# DS133-1_0-B.net
KiCad netlist of a schematic drawn in Altium Designer
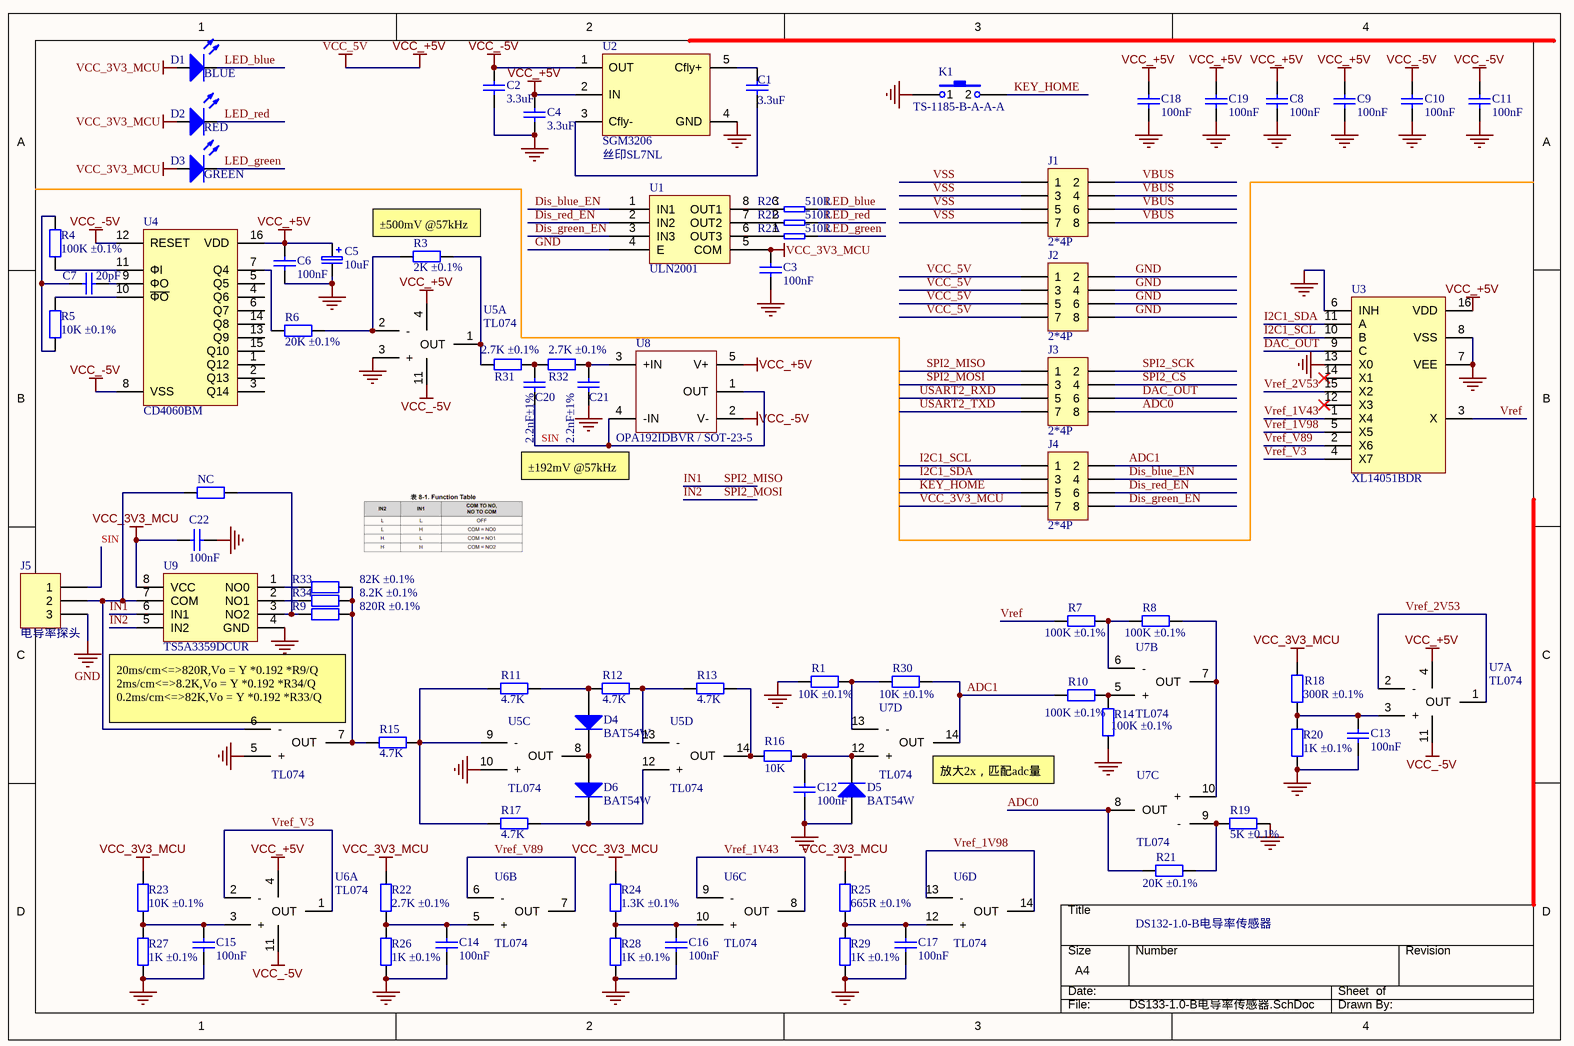
[diagram p0: DS133-1.0-B电导率传感器.SchDoc]

(export (version "E")
  (design (tool "Eeschema 10.0.6"))
  (components
    (comp (ref "C1")
      (value "3.3uF")
      (footprint "0603CAP")
      (description "贴片电容")
      (fields (field (name "Comment") "MLCC 3.3uF 50V ±10％ 0603"))
      (libsource (lib "AD_SCH") (part "MLCC 3.3uF 50V ±10％ 0603"))
    )
    (comp (ref "C2")
      (value "3.3uF")
      (footprint "0603CAP")
      (description "贴片电容")
      (libsource (lib "AD_SCH") (part "MLCC 3.3uF 50V ±10％ 0603"))
    )
    (comp (ref "C3")
      (value "100nF")
      (footprint "0603CAP")
      (description "贴片电容")
      (libsource (lib "AD_SCH") (part "MLCC 100nF 50V ±10％ 0603"))
    )
    (comp (ref "C4")
      (value "3.3uF")
      (footprint "0603CAP")
      (description "贴片电容")
      (fields (field (name "Comment") "MLCC 3.3uF 50V ±10％ 0603"))
      (libsource (lib "AD_SCH") (part "MLCC 3.3uF 50V ±10％ 0603"))
    )
    (comp (ref "C5")
      (value "10uF")
      (footprint "AVX_3216-18(1206)_SMD")
      (description "钽电容")
      (fields (field (name "Comment") "AVX_10uF/16V ±10％(C106)"))
      (libsource (lib "AD_SCH") (part "AVX_10uF/16V ±10％(C106)"))
    )
    (comp (ref "C6")
      (value "100nF")
      (footprint "0603CAP")
      (description "贴片电容")
      (fields (field (name "Comment") "SMDCAP00013"))
      (libsource (lib "AD_SCH") (part "MLCC 100nF 50V ±10％ 0603"))
    )
    (comp (ref "C7")
      (value "20pF")
      (footprint "0603CAP")
      (description "贴片电容")
      (fields (field (name "Comment") "SMDCAP00002"))
      (libsource (lib "AD_SCH") (part "MLCC 20pF 50V ±10％ 0603"))
    )
    (comp (ref "C8")
      (value "100nF")
      (footprint "0603CAP")
      (description "贴片电容")
      (libsource (lib "AD_SCH") (part "MLCC 100nF 50V ±10％ 0603"))
    )
    (comp (ref "C9")
      (value "100nF")
      (footprint "0603CAP")
      (description "贴片电容")
      (libsource (lib "AD_SCH") (part "MLCC 100nF 50V ±10％ 0603"))
    )
    (comp (ref "C10")
      (value "100nF")
      (footprint "0603CAP")
      (description "贴片电容")
      (libsource (lib "AD_SCH") (part "MLCC 100nF 50V ±10％ 0603"))
    )
    (comp (ref "C11")
      (value "100nF")
      (footprint "0603CAP")
      (description "贴片电容")
      (libsource (lib "AD_SCH") (part "MLCC 100nF 50V ±10％ 0603"))
    )
    (comp (ref "C12")
      (value "100nF")
      (footprint "0603CAP")
      (description "贴片电容")
      (libsource (lib "AD_SCH") (part "MLCC 100nF 50V ±10％ 0603"))
    )
    (comp (ref "C13")
      (value "100nF")
      (footprint "0603CAP")
      (description "贴片电容")
      (libsource (lib "AD_SCH") (part "MLCC 100nF 50V ±10％ 0603"))
    )
    (comp (ref "C14")
      (value "100nF")
      (footprint "0603CAP")
      (description "贴片电容")
      (libsource (lib "AD_SCH") (part "MLCC 100nF 50V ±10％ 0603"))
    )
    (comp (ref "C15")
      (value "100nF")
      (footprint "0603CAP")
      (description "贴片电容")
      (libsource (lib "AD_SCH") (part "MLCC 100nF 50V ±10％ 0603"))
    )
    (comp (ref "C16")
      (value "100nF")
      (footprint "0603CAP")
      (description "贴片电容")
      (libsource (lib "AD_SCH") (part "MLCC 100nF 50V ±10％ 0603"))
    )
    (comp (ref "C17")
      (value "100nF")
      (footprint "0603CAP")
      (description "贴片电容")
      (libsource (lib "AD_SCH") (part "MLCC 100nF 50V ±10％ 0603"))
    )
    (comp (ref "C18")
      (value "100nF")
      (footprint "0603CAP")
      (description "贴片电容")
      (libsource (lib "AD_SCH") (part "MLCC 100nF 50V ±10％ 0603"))
    )
    (comp (ref "C19")
      (value "100nF")
      (footprint "0603CAP")
      (description "贴片电容")
      (libsource (lib "AD_SCH") (part "MLCC 100nF 50V ±10％ 0603"))
    )
    (comp (ref "C20")
      (value "2.2nF±1%")
      (footprint "0603CAP")
      (description "贴片电容")
      (fields (field (name "Comment") "MLCC 2.2nF 50V ±1％ 0603"))
      (libsource (lib "AD_SCH") (part "MLCC 2.2nF 50V ±1％ 0603"))
    )
    (comp (ref "C21")
      (value "2.2nF±1%")
      (footprint "0603CAP")
      (description "贴片电容")
      (fields (field (name "Comment") "MLCC 2.2nF 50V ±1％ 0603"))
      (libsource (lib "AD_SCH") (part "MLCC 2.2nF 50V ±1％ 0603"))
    )
    (comp (ref "C22")
      (value "100nF")
      (footprint "0603CAP")
      (description "贴片电容")
      (libsource (lib "AD_SCH") (part "MLCC 100nF 50V ±10％ 0603"))
    )
    (comp (ref "D1")
      (value "BLUE")
      (footprint "LED_0805")
      (description "贴片LED")
      (fields (field (name "Comment") "SMDLED00010"))
      (libsource (lib "AD_SCH") (part "Chip 蓝色LED 0805"))
    )
    (comp (ref "D2")
      (value "RED")
      (footprint "LED_0805")
      (description "贴片LED")
      (fields (field (name "Comment") "SMDLED00003"))
      (libsource (lib "AD_SCH") (part "Chip 红色LED 0805"))
    )
    (comp (ref "D3")
      (value "GREEN")
      (footprint "LED_0805")
      (description "贴片LED")
      (fields (field (name "Comment") "Chip 翠绿LED 0805"))
      (libsource (lib "AD_SCH") (part "Chip 翠绿LED 0805"))
    )
    (comp (ref "D4") (value "BAT54W") (footprint "SOD-123") (libsource (lib "AD_SCH") (part "BAT54W")))
    (comp (ref "D5") (value "BAT54W") (footprint "SOD-123") (libsource (lib "AD_SCH") (part "BAT54W")))
    (comp (ref "D6") (value "BAT54W") (footprint "SOD-123") (libsource (lib "AD_SCH") (part "BAT54W")))
    (comp (ref "J1")
      (value "2*4P")
      (footprint "X1321WVS-2x04J-C40D53")
      (description "双排针2x4P 立贴 1.27mm")
      (fields (field (name "Comment") "X1321WVS-2x04J-C40D53"))
      (libsource (lib "AD_SCH") (part "X1321WVS-2x04J-C40D53"))
    )
    (comp (ref "J2")
      (value "2*4P")
      (footprint "X1321WVS-2x04J-C40D53")
      (description "双排针2x4P 立贴 1.27mm")
      (fields (field (name "Comment") "X1321WVS-2x04J-C40D53"))
      (libsource (lib "AD_SCH") (part "X1321WVS-2x04J-C40D53"))
    )
    (comp (ref "J3")
      (value "2*4P")
      (footprint "X1321WVS-2x04J-C40D53")
      (description "双排针2x4P 立贴 1.27mm")
      (fields (field (name "Comment") "X1321WVS-2x04J-C40D53"))
      (libsource (lib "AD_SCH") (part "X1321WVS-2x04J-C40D53"))
    )
    (comp (ref "J4")
      (value "2*4P")
      (footprint "X1321WVS-2x04J-C40D53")
      (description "双排针2x4P 立贴 1.27mm")
      (fields (field (name "Comment") "X1321WVS-2x04J-C40D53"))
      (libsource (lib "AD_SCH") (part "X1321WVS-2x04J-C40D53"))
    )
    (comp (ref "J5")
      (value "电导率探头")
      (footprint "SIP3")
      (description "单排直针")
      (fields (field (name "Comment") "SL000000042"))
      (libsource (lib "AD_SCH") (part "DIP3 单排直针 间距2.54mm 针长11mm 铜"))
    )
    (comp (ref "K1")
      (value "TS-1185-B-A-A-A")
      (footprint "KEY_TS-1185-x-A-A-A")
      (description "轻触开关")
      (libsource (lib "AD_SCH") (part "TS-1185-B-A-A-A"))
    )
    (comp (ref "NC")
      (value "Chip 0R 1/16W ±1％ 0603")
      (footprint "0603RES")
      (description "贴片电阻")
      (libsource (lib "AD_SCH") (part "Chip 0R 1/16W ±1％ 0603"))
    )
    (comp (ref "R1")
      (value "10K ±0.1%")
      (footprint "0603RES")
      (fields (field (name "Comment") "Chip 10K 1/10W ±0.1％ 0603"))
      (libsource (lib "") (part "Chip 10K 1/10W ±0.1％ 0603_1"))
    )
    (comp (ref "R2")
      (value "510R")
      (footprint "0603RES_Pack4")
      (description "贴片排阻")
      (fields (field (name "Comment") "SMDRES05003"))
      (libsource (lib "AD_SCH") (part "Chip R*4 510R 1/16W ±5％ 0603"))
    )
    (comp (ref "R3")
      (value "2K ±0.1%")
      (footprint "0603RES")
      (fields (field (name "Comment") "Chip 2K 1/10W ±0.1％ 0603"))
      (libsource (lib "AD_SCH") (part "Chip 2K 1/10W ±0.1％ 0603"))
    )
    (comp (ref "R4")
      (value "100K ±0.1%")
      (footprint "0603RES")
      (libsource (lib "") (part "Chip 100K 1/10W ±0.1％ 0603_1"))
    )
    (comp (ref "R5")
      (value "10K ±0.1%")
      (footprint "0603RES")
      (fields (field (name "Comment") "Chip 10K 1/10W ±0.1％ 0603"))
      (libsource (lib "AD_SCH") (part "Chip 10K 1/10W ±0.1％ 0603"))
    )
    (comp (ref "R6")
      (value "20K ±0.1%")
      (footprint "0603RES")
      (fields (field (name "Comment") "Chip 20K 1/10W ±0.1％ 0603"))
      (libsource (lib "AD_SCH") (part "Chip 20K 1/10W ±0.1％ 0603"))
    )
    (comp (ref "R7")
      (value "100K ±0.1%")
      (footprint "0603RES")
      (fields (field (name "Comment") "Chip 100K 1/10W ±0.1％ 0603"))
      (libsource (lib "AD_SCH") (part "Chip 100K 1/10W ±0.1％ 0603"))
    )
    (comp (ref "R8")
      (value "100K ±0.1%")
      (footprint "0603RES")
      (fields (field (name "Comment") "Chip 100K 1/10W ±0.1％ 0603"))
      (libsource (lib "") (part "Chip 100K 1/10W ±0.1％ 0603_2"))
    )
    (comp (ref "R9")
      (value "820R ±0.1%")
      (footprint "0603RES")
      (fields (field (name "Comment") "Chip 820R 1/10W ±0.1％ 0603"))
      (libsource (lib "AD_SCH") (part "Chip 820R 1/10W ±0.1％ 0603"))
    )
    (comp (ref "R10")
      (value "100K ±0.1%")
      (footprint "0603RES")
      (fields (field (name "Comment") "Chip 100K 1/10W ±0.1％ 0603"))
      (libsource (lib "AD_SCH") (part "Chip 100K 1/10W ±0.1％ 0603"))
    )
    (comp (ref "R11")
      (value "4.7K")
      (footprint "0603RES")
      (description "贴片电阻")
      (fields (field (name "Comment") "SMDRES00047"))
      (libsource (lib "AD_SCH") (part "Chip 4.7K 1/10W ±1％ 0603"))
    )
    (comp (ref "R12")
      (value "4.7K")
      (footprint "0603RES")
      (description "贴片电阻")
      (fields (field (name "Comment") "SMDRES00047"))
      (libsource (lib "AD_SCH") (part "Chip 4.7K 1/10W ±1％ 0603"))
    )
    (comp (ref "R13")
      (value "4.7K")
      (footprint "0603RES")
      (description "贴片电阻")
      (fields (field (name "Comment") "SMDRES00047"))
      (libsource (lib "AD_SCH") (part "Chip 4.7K 1/10W ±1％ 0603"))
    )
    (comp (ref "R14")
      (value "100K ±0.1%")
      (footprint "0603RES")
      (fields (field (name "Comment") "Chip 100K 1/10W ±0.1％ 0603"))
      (libsource (lib "") (part "Chip 100K 1/10W ±0.1％ 0603_1"))
    )
    (comp (ref "R15")
      (value "4.7K")
      (footprint "0603RES")
      (description "贴片电阻")
      (fields (field (name "Comment") "SMDRES00047"))
      (libsource (lib "AD_SCH") (part "Chip 4.7K 1/10W ±1％ 0603"))
    )
    (comp (ref "R16")
      (value "10K")
      (footprint "0603RES")
      (description "贴片电阻")
      (fields (field (name "Comment") "Chip 10K 1/16W ±1％ 0603"))
      (libsource (lib "AD_SCH") (part "Chip 10K 1/16W ±1％ 0603"))
    )
    (comp (ref "R17")
      (value "4.7K")
      (footprint "0603RES")
      (description "贴片电阻")
      (fields (field (name "Comment") "SMDRES00047"))
      (libsource (lib "AD_SCH") (part "Chip 4.7K 1/10W ±1％ 0603"))
    )
    (comp (ref "R18")
      (value "300R ±0.1%")
      (footprint "0603RES")
      (libsource (lib "AD_SCH") (part "Chip 300R 1/10W ±0.1％ 0603"))
    )
    (comp (ref "R19")
      (value "5K ±0.1%")
      (footprint "0603RES")
      (fields (field (name "Comment") "Chip 5K 1/10W ±0.1％ 0603"))
      (libsource (lib "AD_SCH") (part "Chip 5K 1/10W ±0.1％ 0603"))
    )
    (comp (ref "R20")
      (value "1K ±0.1%")
      (footprint "0603RES")
      (fields (field (name "Comment") "Chip 1K 1/10W ±0.1％ 0603"))
      (libsource (lib "AD_SCH") (part "Chip 1K 1/10W ±0.1％ 0603"))
    )
    (comp (ref "R21")
      (value "20K ±0.1%")
      (footprint "0603RES")
      (fields (field (name "Comment") "Chip 20K 1/10W ±0.1％ 0603"))
      (libsource (lib "AD_SCH") (part "Chip 20K 1/10W ±0.1％ 0603"))
    )
    (comp (ref "R22")
      (value "2.7K ±0.1%")
      (footprint "0603RES")
      (fields (field (name "Comment") "Chip 2.7K 1/10W ±0.1％ 0603"))
      (libsource (lib "") (part "Chip 2.7K 1/10W ±0.1％ 0603_1"))
    )
    (comp (ref "R23")
      (value "10K ±0.1%")
      (footprint "0603RES")
      (fields (field (name "Comment") "Chip 10K 1/10W ±0.1％ 0603"))
      (libsource (lib "AD_SCH") (part "Chip 10K 1/10W ±0.1％ 0603"))
    )
    (comp (ref "R24")
      (value "1.3K ±0.1%")
      (footprint "0603RES")
      (fields (field (name "Comment") "Chip 1.3K 1/10W ±0.1％ 0603"))
      (libsource (lib "AD_SCH") (part "Chip 1.3K 1/10W ±0.1％ 0603"))
    )
    (comp (ref "R25")
      (value "665R ±0.1%")
      (footprint "0603RES")
      (fields (field (name "Comment") "Chip 665R 1/10W ±0.1％ 0603"))
      (libsource (lib "AD_SCH") (part "Chip 665R 1/10W ±0.1％ 0603"))
    )
    (comp (ref "R26")
      (value "1K ±0.1%")
      (footprint "0603RES")
      (fields (field (name "Comment") "Chip 1K 1/10W ±0.1％ 0603"))
      (libsource (lib "AD_SCH") (part "Chip 1K 1/10W ±0.1％ 0603"))
    )
    (comp (ref "R27")
      (value "1K ±0.1%")
      (footprint "0603RES")
      (fields (field (name "Comment") "Chip 1K 1/10W ±0.1％ 0603"))
      (libsource (lib "AD_SCH") (part "Chip 1K 1/10W ±0.1％ 0603"))
    )
    (comp (ref "R28")
      (value "1K ±0.1%")
      (footprint "0603RES")
      (fields (field (name "Comment") "Chip 1K 1/10W ±0.1％ 0603"))
      (libsource (lib "AD_SCH") (part "Chip 1K 1/10W ±0.1％ 0603"))
    )
    (comp (ref "R29")
      (value "1K ±0.1%")
      (footprint "0603RES")
      (fields (field (name "Comment") "Chip 1K 1/10W ±0.1％ 0603"))
      (libsource (lib "AD_SCH") (part "Chip 1K 1/10W ±0.1％ 0603"))
    )
    (comp (ref "R30")
      (value "10K ±0.1%")
      (footprint "0603RES")
      (fields (field (name "Comment") "Chip 10K 1/10W ±0.1％ 0603"))
      (libsource (lib "") (part "Chip 10K 1/10W ±0.1％ 0603_1"))
    )
    (comp (ref "R31")
      (value "2.7K ±0.1%")
      (footprint "0603RES")
      (fields (field (name "Comment") "Chip 2.7K 1/10W ±0.1％ 0603"))
      (libsource (lib "AD_SCH") (part "Chip 2.7K 1/10W ±0.1％ 0603"))
    )
    (comp (ref "R32")
      (value "2.7K ±0.1%")
      (footprint "0603RES")
      (fields (field (name "Comment") "Chip 2.7K 1/10W ±0.1％ 0603"))
      (libsource (lib "AD_SCH") (part "Chip 2.7K 1/10W ±0.1％ 0603"))
    )
    (comp (ref "R33")
      (value "82K ±0.1%")
      (footprint "0603RES")
      (fields (field (name "Comment") "SMDRES00096"))
      (libsource (lib "AD_SCH") (part "Chip 82K 1/10W ±0.1％ 0603"))
    )
    (comp (ref "R34")
      (value "8.2K ±0.1%")
      (footprint "0603RES")
      (fields (field (name "Comment") "Chip 8.2k 1/10W ±0.1％ 0603"))
      (libsource (lib "AD_SCH") (part "Chip 8.2k 1/10W ±0.1％ 0603"))
    )
    (comp (ref "U1")
      (value "ULN2001")
      (footprint "SO-8")
      (description "电机驱动芯片")
      (fields (field (name "Comment") "SMDIC000018"))
      (libsource (lib "AD_SCH") (part "ULN2001 SOP-8"))
    )
    (comp (ref "U2")
      (value "SGM3206")
      (footprint "SOT23-5")
      (description "电荷泵芯片")
      (fields (field (name "ALTIUM_VALUE") "丝印SL7NL"))
      (libsource (lib "AD_SCH") (part "SGM3206"))
    )
    (comp (ref "U3")
      (value "XL14051BDR")
      (footprint "SO-16")
      (description "XINLUDA(信路达)\r\nXL14051BDR\r\nSOP-16​")
      (libsource (lib "AD_SCH") (part "XL14051BDR"))
    )
    (comp (ref "U4")
      (value "CD4060BM")
      (footprint "SO-16")
      (description "HGSEMI(华冠)\r\nCD4060BM/TR\r\nSOP-16")
      (libsource (lib "AD_SCH") (part "CD4060BM"))
    )
    (comp (ref "U5")
      (value "TL074")
      (footprint "SO-14")
      (description "TI\r\nTL074CDR\r\nSOIC-14")
      (libsource (lib "AD_SCH") (part "TL074"))
    )
    (comp (ref "U6")
      (value "TL074")
      (footprint "SO-14")
      (description "TI\r\nTL074CDR\r\nSOIC-14")
      (libsource (lib "AD_SCH") (part "TL074"))
    )
    (comp (ref "U7")
      (value "TL074")
      (footprint "SO-14")
      (description "TI\r\nTL074CDR\r\nSOIC-14")
      (libsource (lib "AD_SCH") (part "TL074"))
    )
    (comp (ref "U8")
      (value "OPA192IDBVR / SOT-23-5")
      (footprint "SOT23-5")
      (description "低失调电压: 65 µV（最大值）\r\n低输入偏置电流: 1 pA（最大值）\r\n单电源供电：2.7 V至5.5 V")
      (libsource (lib "AD_SCH") (part "AD8605"))
    )
    (comp (ref "U9")
      (value "TS5A3359DCUR")
      (footprint "VSSOP-8")
      (description "单刀三掷(SP3T)模拟开关")
      (libsource (lib "AD_SCH") (part "TS5A3359DCUR"))
    )
  )
  (nets
    (net (code "1") (name "/ADC0") (class "Default")
      (node (ref "J3") (pin "8") (pinfunction "8_8") (pintype "passive"))
      (node (ref "R21") (pin "1") (pinfunction "1_1") (pintype "passive"))
      (node (ref "U7") (pin "8") (pinfunction "OUT_8") (pintype "passive"))
    )
    (net (code "2") (name "/ADC1") (class "Default")
      (node (ref "J4") (pin "2") (pinfunction "2_2") (pintype "passive"))
      (node (ref "R10") (pin "1") (pinfunction "1_1") (pintype "passive"))
      (node (ref "R30") (pin "2") (pinfunction "2_2") (pintype "passive"))
      (node (ref "U7") (pin "14") (pinfunction "OUT_14") (pintype "passive"))
    )
    (net (code "3") (name "/DAC_OUT") (class "Default")
      (node (ref "J3") (pin "6") (pinfunction "6_6") (pintype "passive"))
      (node (ref "U3") (pin "9") (pinfunction "C_9") (pintype "passive"))
    )
    (net (code "4") (name "/Dis_blue_EN") (class "Default")
      (node (ref "J4") (pin "4") (pinfunction "4_4") (pintype "passive"))
      (node (ref "U1") (pin "1") (pinfunction "IN1_1") (pintype "passive"))
    )
    (net (code "5") (name "/Dis_green_EN") (class "Default")
      (node (ref "J4") (pin "8") (pinfunction "8_8") (pintype "passive"))
      (node (ref "U1") (pin "3") (pinfunction "IN3_3") (pintype "passive"))
    )
    (net (code "6") (name "/Dis_red_EN") (class "Default")
      (node (ref "J4") (pin "6") (pinfunction "6_6") (pintype "passive"))
      (node (ref "U1") (pin "2") (pinfunction "IN2_2") (pintype "passive"))
    )
    (net (code "7") (name "/I2C1_SCL") (class "Default")
      (node (ref "J4") (pin "1") (pinfunction "1_1") (pintype "passive"))
      (node (ref "U3") (pin "10") (pinfunction "B_10") (pintype "passive"))
    )
    (net (code "8") (name "/I2C1_SDA") (class "Default")
      (node (ref "J4") (pin "3") (pinfunction "3_3") (pintype "passive"))
      (node (ref "U3") (pin "11") (pinfunction "A_11") (pintype "passive"))
    )
    (net (code "9") (name "/IN1") (class "Default")
      (node (ref "J3") (pin "1") (pinfunction "1_1") (pintype "passive"))
      (node (ref "U9") (pin "6") (pinfunction "IN1_6") (pintype "passive"))
    )
    (net (code "10") (name "/IN2") (class "Default")
      (node (ref "J3") (pin "3") (pinfunction "3_3") (pintype "passive"))
      (node (ref "U9") (pin "5") (pinfunction "IN2_5") (pintype "passive"))
    )
    (net (code "11") (name "/KEY_HOME") (class "Default")
      (node (ref "J4") (pin "5") (pinfunction "5_5") (pintype "passive"))
      (node (ref "K1") (pin "2") (pinfunction "2_2") (pintype "passive"))
    )
    (net (code "12") (name "/LED_blue") (class "Default")
      (node (ref "D1") (pin "2") (pinfunction "K_2") (pintype "passive"))
      (node (ref "R2") (pin "6") (pinfunction "6_6") (pintype "passive"))
    )
    (net (code "13") (name "/LED_green") (class "Default")
      (node (ref "D3") (pin "2") (pinfunction "K_2") (pintype "passive"))
      (node (ref "R2") (pin "8") (pinfunction "8_8") (pintype "passive"))
    )
    (net (code "14") (name "/LED_red") (class "Default")
      (node (ref "D2") (pin "2") (pinfunction "K_2") (pintype "passive"))
      (node (ref "R2") (pin "7") (pinfunction "7_7") (pintype "passive"))
    )
    (net (code "15") (name "/SIN") (class "Default")
      (node (ref "C20") (pin "1") (pinfunction "1_1") (pintype "passive"))
      (node (ref "J5") (pin "1") (pinfunction "1_1") (pintype "passive"))
      (node (ref "U8") (pin "1") (pinfunction "OUT_1") (pintype "passive"))
      (node (ref "U8") (pin "4") (pinfunction "-IN_4") (pintype "passive"))
    )
    (net (code "16") (name "/SPI2_CS") (class "Default")
      (node (ref "J3") (pin "4") (pinfunction "4_4") (pintype "passive"))
    )
    (net (code "17") (name "/SPI2_SCK") (class "Default")
      (node (ref "J3") (pin "2") (pinfunction "2_2") (pintype "passive"))
    )
    (net (code "18") (name "/USART2_RXD") (class "Default")
      (node (ref "J3") (pin "5") (pinfunction "5_5") (pintype "passive"))
    )
    (net (code "19") (name "/USART2_TXD") (class "Default")
      (node (ref "J3") (pin "7") (pinfunction "7_7") (pintype "passive"))
    )
    (net (code "20") (name "/VBUS") (class "Default")
      (node (ref "J1") (pin "2") (pinfunction "2_2") (pintype "passive"))
      (node (ref "J1") (pin "4") (pinfunction "4_4") (pintype "passive"))
      (node (ref "J1") (pin "6") (pinfunction "6_6") (pintype "passive"))
      (node (ref "J1") (pin "8") (pinfunction "8_8") (pintype "passive"))
    )
    (net (code "21") (name "/VSS") (class "Default")
      (node (ref "J1") (pin "1") (pinfunction "1_1") (pintype "passive"))
      (node (ref "J1") (pin "3") (pinfunction "3_3") (pintype "passive"))
      (node (ref "J1") (pin "5") (pinfunction "5_5") (pintype "passive"))
      (node (ref "J1") (pin "7") (pinfunction "7_7") (pintype "passive"))
    )
    (net (code "22") (name "/Vref") (class "Default")
      (node (ref "R7") (pin "1") (pinfunction "1_1") (pintype "passive"))
      (node (ref "U3") (pin "3") (pinfunction "X_3") (pintype "passive"))
    )
    (net (code "23") (name "/Vref_1V43") (class "Default")
      (node (ref "U3") (pin "1") (pinfunction "X4_1") (pintype "passive"))
      (node (ref "U6") (pin "8") (pinfunction "OUT_8") (pintype "passive"))
      (node (ref "U6") (pin "9") (pinfunction "-_9") (pintype "passive"))
    )
    (net (code "24") (name "/Vref_1V98") (class "Default")
      (node (ref "U3") (pin "5") (pinfunction "X5_5") (pintype "passive"))
      (node (ref "U6") (pin "13") (pinfunction "-_13") (pintype "passive"))
      (node (ref "U6") (pin "14") (pinfunction "OUT_14") (pintype "passive"))
    )
    (net (code "25") (name "/Vref_2V53") (class "Default")
      (node (ref "U3") (pin "15") (pinfunction "X2_15") (pintype "passive"))
      (node (ref "U7") (pin "1") (pinfunction "OUT_1") (pintype "passive"))
      (node (ref "U7") (pin "2") (pinfunction "-_2") (pintype "passive"))
    )
    (net (code "26") (name "/Vref_V3") (class "Default")
      (node (ref "U3") (pin "4") (pinfunction "X7_4") (pintype "passive"))
      (node (ref "U6") (pin "1") (pinfunction "OUT_1") (pintype "passive"))
      (node (ref "U6") (pin "2") (pinfunction "-_2") (pintype "passive"))
    )
    (net (code "27") (name "/Vref_V89") (class "Default")
      (node (ref "U3") (pin "2") (pinfunction "X6_2") (pintype "passive"))
      (node (ref "U6") (pin "6") (pinfunction "-_6") (pintype "passive"))
      (node (ref "U6") (pin "7") (pinfunction "OUT_7") (pintype "passive"))
    )
    (net (code "28") (name "GND") (class "Default")
      (node (ref "C10") (pin "1") (pinfunction "1_1") (pintype "passive"))
      (node (ref "C11") (pin "1") (pinfunction "1_1") (pintype "passive"))
      (node (ref "C12") (pin "1") (pinfunction "1_1") (pintype "passive"))
      (node (ref "C13") (pin "2") (pinfunction "2_2") (pintype "passive"))
      (node (ref "C14") (pin "2") (pinfunction "2_2") (pintype "passive"))
      (node (ref "C15") (pin "2") (pinfunction "2_2") (pintype "passive"))
      (node (ref "C16") (pin "2") (pinfunction "2_2") (pintype "passive"))
      (node (ref "C17") (pin "2") (pinfunction "2_2") (pintype "passive"))
      (node (ref "C18") (pin "1") (pinfunction "1_1") (pintype "passive"))
      (node (ref "C19") (pin "1") (pinfunction "1_1") (pintype "passive"))
      (node (ref "C2") (pin "2") (pinfunction "2_2") (pintype "passive"))
      (node (ref "C21") (pin "1") (pinfunction "1_1") (pintype "passive"))
      (node (ref "C22") (pin "2") (pinfunction "2_2") (pintype "passive"))
      (node (ref "C3") (pin "1") (pinfunction "1_1") (pintype "passive"))
      (node (ref "C4") (pin "2") (pinfunction "2_2") (pintype "passive"))
      (node (ref "C5") (pin "2") (pinfunction "2_2") (pintype "passive"))
      (node (ref "C6") (pin "2") (pinfunction "2_2") (pintype "passive"))
      (node (ref "C8") (pin "1") (pinfunction "1_1") (pintype "passive"))
      (node (ref "C9") (pin "1") (pinfunction "1_1") (pintype "passive"))
      (node (ref "D5") (pin "1") (pinfunction "A_1") (pintype "passive"))
      (node (ref "J2") (pin "2") (pinfunction "2_2") (pintype "passive"))
      (node (ref "J2") (pin "4") (pinfunction "4_4") (pintype "passive"))
      (node (ref "J2") (pin "6") (pinfunction "6_6") (pintype "passive"))
      (node (ref "J2") (pin "8") (pinfunction "8_8") (pintype "passive"))
      (node (ref "J5") (pin "3") (pinfunction "3_3") (pintype "passive"))
      (node (ref "K1") (pin "1") (pinfunction "1_1") (pintype "passive"))
      (node (ref "R1") (pin "1") (pinfunction "1_1") (pintype "passive"))
      (node (ref "R14") (pin "1") (pinfunction "1_1") (pintype "passive"))
      (node (ref "R19") (pin "2") (pinfunction "2_2") (pintype "passive"))
      (node (ref "R20") (pin "1") (pinfunction "1_1") (pintype "passive"))
      (node (ref "R26") (pin "1") (pinfunction "1_1") (pintype "passive"))
      (node (ref "R27") (pin "1") (pinfunction "1_1") (pintype "passive"))
      (node (ref "R28") (pin "1") (pinfunction "1_1") (pintype "passive"))
      (node (ref "R29") (pin "1") (pinfunction "1_1") (pintype "passive"))
      (node (ref "U1") (pin "4") (pinfunction "E_4") (pintype "passive"))
      (node (ref "U2") (pin "4") (pinfunction "GND_4") (pintype "passive"))
      (node (ref "U3") (pin "13") (pinfunction "X0_13") (pintype "passive"))
      (node (ref "U3") (pin "6") (pinfunction "INH_6") (pintype "passive"))
      (node (ref "U3") (pin "7") (pinfunction "VEE_7") (pintype "passive"))
      (node (ref "U3") (pin "8") (pinfunction "VSS_8") (pintype "passive"))
      (node (ref "U5") (pin "10") (pinfunction "+_10") (pintype "passive"))
      (node (ref "U5") (pin "3") (pinfunction "+_3") (pintype "passive"))
      (node (ref "U5") (pin "5") (pinfunction "+_5") (pintype "passive"))
      (node (ref "U9") (pin "4") (pinfunction "GND_4") (pintype "passive"))
    )
    (net (code "29") (name "Net-(C7-Pad2)") (class "Default")
      (node (ref "C7") (pin "2") (pinfunction "2_2") (pintype "passive"))
      (node (ref "R4") (pin "2") (pinfunction "2_2") (pintype "passive"))
      (node (ref "R5") (pin "1") (pinfunction "1_1") (pintype "passive"))
    )
    (net (code "30") (name "Net-(C20-Pad2)") (class "Default")
      (node (ref "C20") (pin "2") (pinfunction "2_2") (pintype "passive"))
      (node (ref "R31") (pin "2") (pinfunction "2_2") (pintype "passive"))
      (node (ref "R32") (pin "1") (pinfunction "1_1") (pintype "passive"))
    )
    (net (code "31") (name "Net-(D4-A)") (class "Default")
      (node (ref "D4") (pin "1") (pinfunction "A_1") (pintype "passive"))
      (node (ref "R11") (pin "2") (pinfunction "2_2") (pintype "passive"))
      (node (ref "R12") (pin "1") (pinfunction "1_1") (pintype "passive"))
    )
    (net (code "32") (name "Net-(D4-K)") (class "Default")
      (node (ref "D4") (pin "2") (pinfunction "K_2") (pintype "passive"))
      (node (ref "D6") (pin "1") (pinfunction "A_1") (pintype "passive"))
      (node (ref "U5") (pin "8") (pinfunction "OUT_8") (pintype "passive"))
    )
    (net (code "33") (name "Net-(D5-K)") (class "Default")
      (node (ref "C12") (pin "2") (pinfunction "2_2") (pintype "passive"))
      (node (ref "D5") (pin "2") (pinfunction "K_2") (pintype "passive"))
      (node (ref "R16") (pin "2") (pinfunction "2_2") (pintype "passive"))
      (node (ref "U7") (pin "12") (pinfunction "+_12") (pintype "passive"))
    )
    (net (code "34") (name "Net-(D6-K)") (class "Default")
      (node (ref "D6") (pin "2") (pinfunction "K_2") (pintype "passive"))
      (node (ref "R17") (pin "2") (pinfunction "2_2") (pintype "passive"))
      (node (ref "U5") (pin "12") (pinfunction "+_12") (pintype "passive"))
    )
    (net (code "35") (name "Net-(U1-OUT1)") (class "Default")
      (node (ref "R2") (pin "3") (pinfunction "3_3") (pintype "passive"))
      (node (ref "U1") (pin "8") (pinfunction "OUT1_8") (pintype "passive"))
    )
    (net (code "36") (name "Net-(U1-OUT2)") (class "Default")
      (node (ref "R2") (pin "2") (pinfunction "2_2") (pintype "passive"))
      (node (ref "U1") (pin "7") (pinfunction "OUT2_7") (pintype "passive"))
    )
    (net (code "37") (name "Net-(U1-OUT3)") (class "Default")
      (node (ref "R2") (pin "1") (pinfunction "1_1") (pintype "passive"))
      (node (ref "U1") (pin "6") (pinfunction "OUT3_6") (pintype "passive"))
    )
    (net (code "38") (name "Net-(U2-Cfly+)") (class "Default")
      (node (ref "C1") (pin "2") (pinfunction "2_2") (pintype "passive"))
      (node (ref "U2") (pin "5") (pinfunction "Cfly+_5") (pintype "passive"))
    )
    (net (code "39") (name "Net-(U2-Cfly-)") (class "Default")
      (node (ref "C1") (pin "1") (pinfunction "1_1") (pintype "passive"))
      (node (ref "U2") (pin "3") (pinfunction "Cfly-_3") (pintype "passive"))
    )
    (net (code "40") (name "Net-(U4-Q4)") (class "Default")
      (node (ref "R6") (pin "1") (pinfunction "1_1") (pintype "passive"))
      (node (ref "U4") (pin "7") (pinfunction "Q4_7") (pintype "passive"))
    )
    (net (code "41") (name "Net-(U4-~{ΦO})") (class "Default")
      (node (ref "R5") (pin "2") (pinfunction "2_2") (pintype "passive"))
      (node (ref "U4") (pin "10") (pinfunction "~{ΦO}_10") (pintype "passive"))
    )
    (net (code "42") (name "Net-(U4-ΦI)") (class "Default")
      (node (ref "R4") (pin "1") (pinfunction "1_1") (pintype "passive"))
      (node (ref "U4") (pin "11") (pinfunction "ΦI_11") (pintype "passive"))
    )
    (net (code "43") (name "Net-(U4-ΦO)") (class "Default")
      (node (ref "C7") (pin "1") (pinfunction "1_1") (pintype "passive"))
      (node (ref "U4") (pin "9") (pinfunction "ΦO_9") (pintype "passive"))
    )
    (net (code "44") (name "Net-(U5A--)") (class "Default")
      (node (ref "R3") (pin "1") (pinfunction "1_1") (pintype "passive"))
      (node (ref "R6") (pin "2") (pinfunction "2_2") (pintype "passive"))
      (node (ref "U5") (pin "2") (pinfunction "-_2") (pintype "passive"))
    )
    (net (code "45") (name "Net-(U5A-OUT)") (class "Default")
      (node (ref "R3") (pin "2") (pinfunction "2_2") (pintype "passive"))
      (node (ref "R31") (pin "1") (pinfunction "1_1") (pintype "passive"))
      (node (ref "U5") (pin "1") (pinfunction "OUT_1") (pintype "passive"))
    )
    (net (code "46") (name "Net-(U5B--)") (class "Default")
      (node (ref "J5") (pin "2") (pinfunction "2_2") (pintype "passive"))
      (node (ref "NC") (pin "1") (pinfunction "1_1") (pintype "passive"))
      (node (ref "U5") (pin "6") (pinfunction "-_6") (pintype "passive"))
      (node (ref "U9") (pin "7") (pinfunction "COM_7") (pintype "passive"))
    )
    (net (code "47") (name "Net-(U5B-OUT)") (class "Default")
      (node (ref "R15") (pin "1") (pinfunction "1_1") (pintype "passive"))
      (node (ref "R33") (pin "2") (pinfunction "2_2") (pintype "passive"))
      (node (ref "R34") (pin "2") (pinfunction "2_2") (pintype "passive"))
      (node (ref "R9") (pin "2") (pinfunction "2_2") (pintype "passive"))
      (node (ref "U5") (pin "7") (pinfunction "OUT_7") (pintype "passive"))
    )
    (net (code "48") (name "Net-(U5C--)") (class "Default")
      (node (ref "R11") (pin "1") (pinfunction "1_1") (pintype "passive"))
      (node (ref "R15") (pin "2") (pinfunction "2_2") (pintype "passive"))
      (node (ref "R17") (pin "1") (pinfunction "1_1") (pintype "passive"))
      (node (ref "U5") (pin "9") (pinfunction "-_9") (pintype "passive"))
    )
    (net (code "49") (name "Net-(U5D--)") (class "Default")
      (node (ref "R12") (pin "2") (pinfunction "2_2") (pintype "passive"))
      (node (ref "R13") (pin "1") (pinfunction "1_1") (pintype "passive"))
      (node (ref "U5") (pin "13") (pinfunction "-_13") (pintype "passive"))
    )
    (net (code "50") (name "Net-(U5D-OUT)") (class "Default")
      (node (ref "R13") (pin "2") (pinfunction "2_2") (pintype "passive"))
      (node (ref "R16") (pin "1") (pinfunction "1_1") (pintype "passive"))
      (node (ref "U5") (pin "14") (pinfunction "OUT_14") (pintype "passive"))
    )
    (net (code "51") (name "Net-(U6A-+)") (class "Default")
      (node (ref "C15") (pin "1") (pinfunction "1_1") (pintype "passive"))
      (node (ref "R23") (pin "1") (pinfunction "1_1") (pintype "passive"))
      (node (ref "R27") (pin "2") (pinfunction "2_2") (pintype "passive"))
      (node (ref "U6") (pin "3") (pinfunction "+_3") (pintype "passive"))
    )
    (net (code "52") (name "Net-(U6B-+)") (class "Default")
      (node (ref "C14") (pin "1") (pinfunction "1_1") (pintype "passive"))
      (node (ref "R22") (pin "1") (pinfunction "1_1") (pintype "passive"))
      (node (ref "R26") (pin "2") (pinfunction "2_2") (pintype "passive"))
      (node (ref "U6") (pin "5") (pinfunction "+_5") (pintype "passive"))
    )
    (net (code "53") (name "Net-(U6C-+)") (class "Default")
      (node (ref "C16") (pin "1") (pinfunction "1_1") (pintype "passive"))
      (node (ref "R24") (pin "1") (pinfunction "1_1") (pintype "passive"))
      (node (ref "R28") (pin "2") (pinfunction "2_2") (pintype "passive"))
      (node (ref "U6") (pin "10") (pinfunction "+_10") (pintype "passive"))
    )
    (net (code "54") (name "Net-(U6D-+)") (class "Default")
      (node (ref "C17") (pin "1") (pinfunction "1_1") (pintype "passive"))
      (node (ref "R25") (pin "1") (pinfunction "1_1") (pintype "passive"))
      (node (ref "R29") (pin "2") (pinfunction "2_2") (pintype "passive"))
      (node (ref "U6") (pin "12") (pinfunction "+_12") (pintype "passive"))
    )
    (net (code "55") (name "Net-(U7A-+)") (class "Default")
      (node (ref "C13") (pin "1") (pinfunction "1_1") (pintype "passive"))
      (node (ref "R18") (pin "1") (pinfunction "1_1") (pintype "passive"))
      (node (ref "R20") (pin "2") (pinfunction "2_2") (pintype "passive"))
      (node (ref "U7") (pin "3") (pinfunction "+_3") (pintype "passive"))
    )
    (net (code "56") (name "Net-(U7B-+)") (class "Default")
      (node (ref "R10") (pin "2") (pinfunction "2_2") (pintype "passive"))
      (node (ref "R14") (pin "2") (pinfunction "2_2") (pintype "passive"))
      (node (ref "U7") (pin "5") (pinfunction "+_5") (pintype "passive"))
    )
    (net (code "57") (name "Net-(U7B--)") (class "Default")
      (node (ref "R7") (pin "2") (pinfunction "2_2") (pintype "passive"))
      (node (ref "R8") (pin "2") (pinfunction "2_2") (pintype "passive"))
      (node (ref "U7") (pin "6") (pinfunction "-_6") (pintype "passive"))
    )
    (net (code "58") (name "Net-(U7B-OUT)") (class "Default")
      (node (ref "R8") (pin "1") (pinfunction "1_1") (pintype "passive"))
      (node (ref "U7") (pin "10") (pinfunction "+_10") (pintype "passive"))
      (node (ref "U7") (pin "7") (pinfunction "OUT_7") (pintype "passive"))
    )
    (net (code "59") (name "Net-(U7C--)") (class "Default")
      (node (ref "R19") (pin "1") (pinfunction "1_1") (pintype "passive"))
      (node (ref "R21") (pin "2") (pinfunction "2_2") (pintype "passive"))
      (node (ref "U7") (pin "9") (pinfunction "-_9") (pintype "passive"))
    )
    (net (code "60") (name "Net-(U7D--)") (class "Default")
      (node (ref "R1") (pin "2") (pinfunction "2_2") (pintype "passive"))
      (node (ref "R30") (pin "1") (pinfunction "1_1") (pintype "passive"))
      (node (ref "U7") (pin "13") (pinfunction "-_13") (pintype "passive"))
    )
    (net (code "61") (name "Net-(U8-+IN)") (class "Default")
      (node (ref "C21") (pin "2") (pinfunction "2_2") (pintype "passive"))
      (node (ref "R32") (pin "2") (pinfunction "2_2") (pintype "passive"))
      (node (ref "U8") (pin "3") (pinfunction "+IN_3") (pintype "passive"))
    )
    (net (code "62") (name "Net-(U9-NO0)") (class "Default")
      (node (ref "R33") (pin "1") (pinfunction "1_1") (pintype "passive"))
      (node (ref "U9") (pin "1") (pinfunction "NO0_1") (pintype "passive"))
    )
    (net (code "63") (name "Net-(U9-NO1)") (class "Default")
      (node (ref "R34") (pin "1") (pinfunction "1_1") (pintype "passive"))
      (node (ref "U9") (pin "2") (pinfunction "NO1_2") (pintype "passive"))
    )
    (net (code "64") (name "Net-(U9-NO2)") (class "Default")
      (node (ref "NC") (pin "2") (pinfunction "2_2") (pintype "passive"))
      (node (ref "R9") (pin "1") (pinfunction "1_1") (pintype "passive"))
      (node (ref "U9") (pin "3") (pinfunction "NO2_3") (pintype "passive"))
    )
    (net (code "65") (name "VCC_+5V") (class "Default")
      (node (ref "C18") (pin "2") (pinfunction "2_2") (pintype "passive"))
      (node (ref "C19") (pin "2") (pinfunction "2_2") (pintype "passive"))
      (node (ref "C4") (pin "1") (pinfunction "1_1") (pintype "passive"))
      (node (ref "C5") (pin "1") (pinfunction "1_1") (pintype "passive"))
      (node (ref "C6") (pin "1") (pinfunction "1_1") (pintype "passive"))
      (node (ref "C8") (pin "2") (pinfunction "2_2") (pintype "passive"))
      (node (ref "C9") (pin "2") (pinfunction "2_2") (pintype "passive"))
      (node (ref "J2") (pin "1") (pinfunction "1_1") (pintype "passive"))
      (node (ref "J2") (pin "3") (pinfunction "3_3") (pintype "passive"))
      (node (ref "J2") (pin "5") (pinfunction "5_5") (pintype "passive"))
      (node (ref "J2") (pin "7") (pinfunction "7_7") (pintype "passive"))
      (node (ref "U2") (pin "2") (pinfunction "IN_2") (pintype "passive"))
      (node (ref "U3") (pin "16") (pinfunction "VDD_16") (pintype "passive"))
      (node (ref "U4") (pin "16") (pinfunction "VDD_16") (pintype "passive"))
      (node (ref "U5") (pin "4") (pinfunction "VCC_4") (pintype "passive"))
      (node (ref "U6") (pin "4") (pinfunction "VCC_4") (pintype "passive"))
      (node (ref "U7") (pin "4") (pinfunction "VCC_4") (pintype "passive"))
      (node (ref "U8") (pin "5") (pinfunction "V+_5") (pintype "passive"))
    )
    (net (code "66") (name "VCC_-5V") (class "Default")
      (node (ref "C10") (pin "2") (pinfunction "2_2") (pintype "passive"))
      (node (ref "C11") (pin "2") (pinfunction "2_2") (pintype "passive"))
      (node (ref "C2") (pin "1") (pinfunction "1_1") (pintype "passive"))
      (node (ref "U2") (pin "1") (pinfunction "OUT_1") (pintype "passive"))
      (node (ref "U4") (pin "12") (pinfunction "RESET_12") (pintype "passive"))
      (node (ref "U4") (pin "8") (pinfunction "VSS_8") (pintype "passive"))
      (node (ref "U5") (pin "11") (pinfunction "GND_11") (pintype "passive"))
      (node (ref "U6") (pin "11") (pinfunction "GND_11") (pintype "passive"))
      (node (ref "U7") (pin "11") (pinfunction "GND_11") (pintype "passive"))
      (node (ref "U8") (pin "2") (pinfunction "V-_2") (pintype "passive"))
    )
    (net (code "67") (name "VCC_3V3_MCU") (class "Default")
      (node (ref "C22") (pin "1") (pinfunction "1_1") (pintype "passive"))
      (node (ref "C3") (pin "2") (pinfunction "2_2") (pintype "passive"))
      (node (ref "D1") (pin "1") (pinfunction "A_1") (pintype "passive"))
      (node (ref "D2") (pin "1") (pinfunction "A_1") (pintype "passive"))
      (node (ref "D3") (pin "1") (pinfunction "A_1") (pintype "passive"))
      (node (ref "J4") (pin "7") (pinfunction "7_7") (pintype "passive"))
      (node (ref "R18") (pin "2") (pinfunction "2_2") (pintype "passive"))
      (node (ref "R22") (pin "2") (pinfunction "2_2") (pintype "passive"))
      (node (ref "R23") (pin "2") (pinfunction "2_2") (pintype "passive"))
      (node (ref "R24") (pin "2") (pinfunction "2_2") (pintype "passive"))
      (node (ref "R25") (pin "2") (pinfunction "2_2") (pintype "passive"))
      (node (ref "U1") (pin "5") (pinfunction "COM_5") (pintype "passive"))
      (node (ref "U9") (pin "8") (pinfunction "VCC_8") (pintype "passive"))
    )
    (net (code "68") (name "unconnected-(U3-X1-Pad14)") (class "Default")
      (node (ref "U3") (pin "14") (pinfunction "X1_14") (pintype "passive+no_connect"))
    )
    (net (code "69") (name "unconnected-(U3-X3-Pad12)") (class "Default")
      (node (ref "U3") (pin "12") (pinfunction "X3_12") (pintype "passive+no_connect"))
    )
    (net (code "70") (name "unconnected-(U4-Q5-Pad5)") (class "Default")
      (node (ref "U4") (pin "5") (pinfunction "Q5_5") (pintype "passive"))
    )
    (net (code "71") (name "unconnected-(U4-Q6-Pad4)") (class "Default")
      (node (ref "U4") (pin "4") (pinfunction "Q6_4") (pintype "passive"))
    )
    (net (code "72") (name "unconnected-(U4-Q7-Pad6)") (class "Default")
      (node (ref "U4") (pin "6") (pinfunction "Q7_6") (pintype "passive"))
    )
    (net (code "73") (name "unconnected-(U4-Q8-Pad14)") (class "Default")
      (node (ref "U4") (pin "14") (pinfunction "Q8_14") (pintype "passive"))
    )
    (net (code "74") (name "unconnected-(U4-Q9-Pad13)") (class "Default")
      (node (ref "U4") (pin "13") (pinfunction "Q9_13") (pintype "passive"))
    )
    (net (code "75") (name "unconnected-(U4-Q10-Pad15)") (class "Default")
      (node (ref "U4") (pin "15") (pinfunction "Q10_15") (pintype "passive"))
    )
    (net (code "76") (name "unconnected-(U4-Q12-Pad1)") (class "Default")
      (node (ref "U4") (pin "1") (pinfunction "Q12_1") (pintype "passive"))
    )
    (net (code "77") (name "unconnected-(U4-Q13-Pad2)") (class "Default")
      (node (ref "U4") (pin "2") (pinfunction "Q13_2") (pintype "passive"))
    )
    (net (code "78") (name "unconnected-(U4-Q14-Pad3)") (class "Default")
      (node (ref "U4") (pin "3") (pinfunction "Q14_3") (pintype "passive"))
    )
  )
)
